# arduino_block.net
KiCad netlist of a schematic drawn in EAGLE
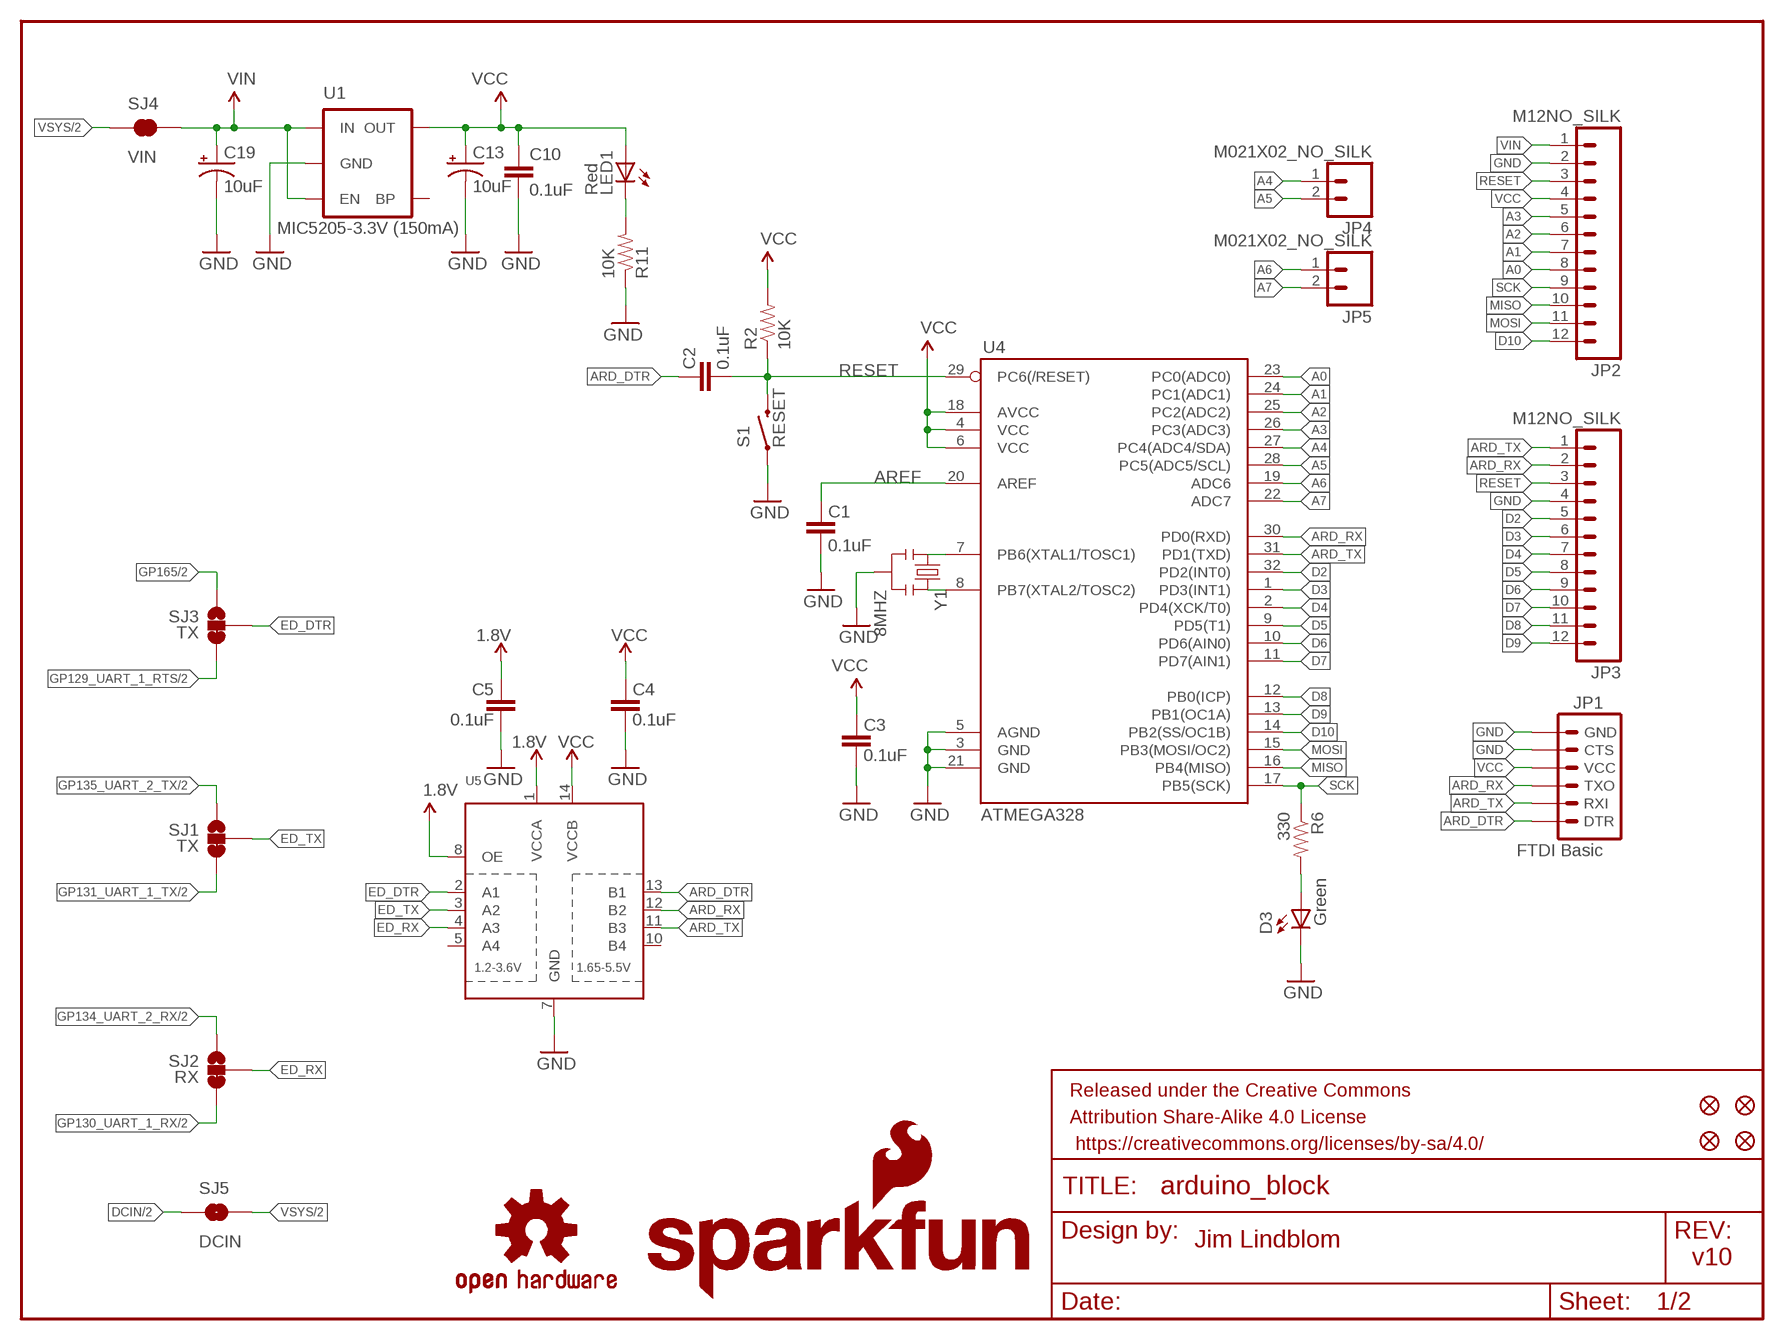
[diagram p0: schematic, sheet 1]
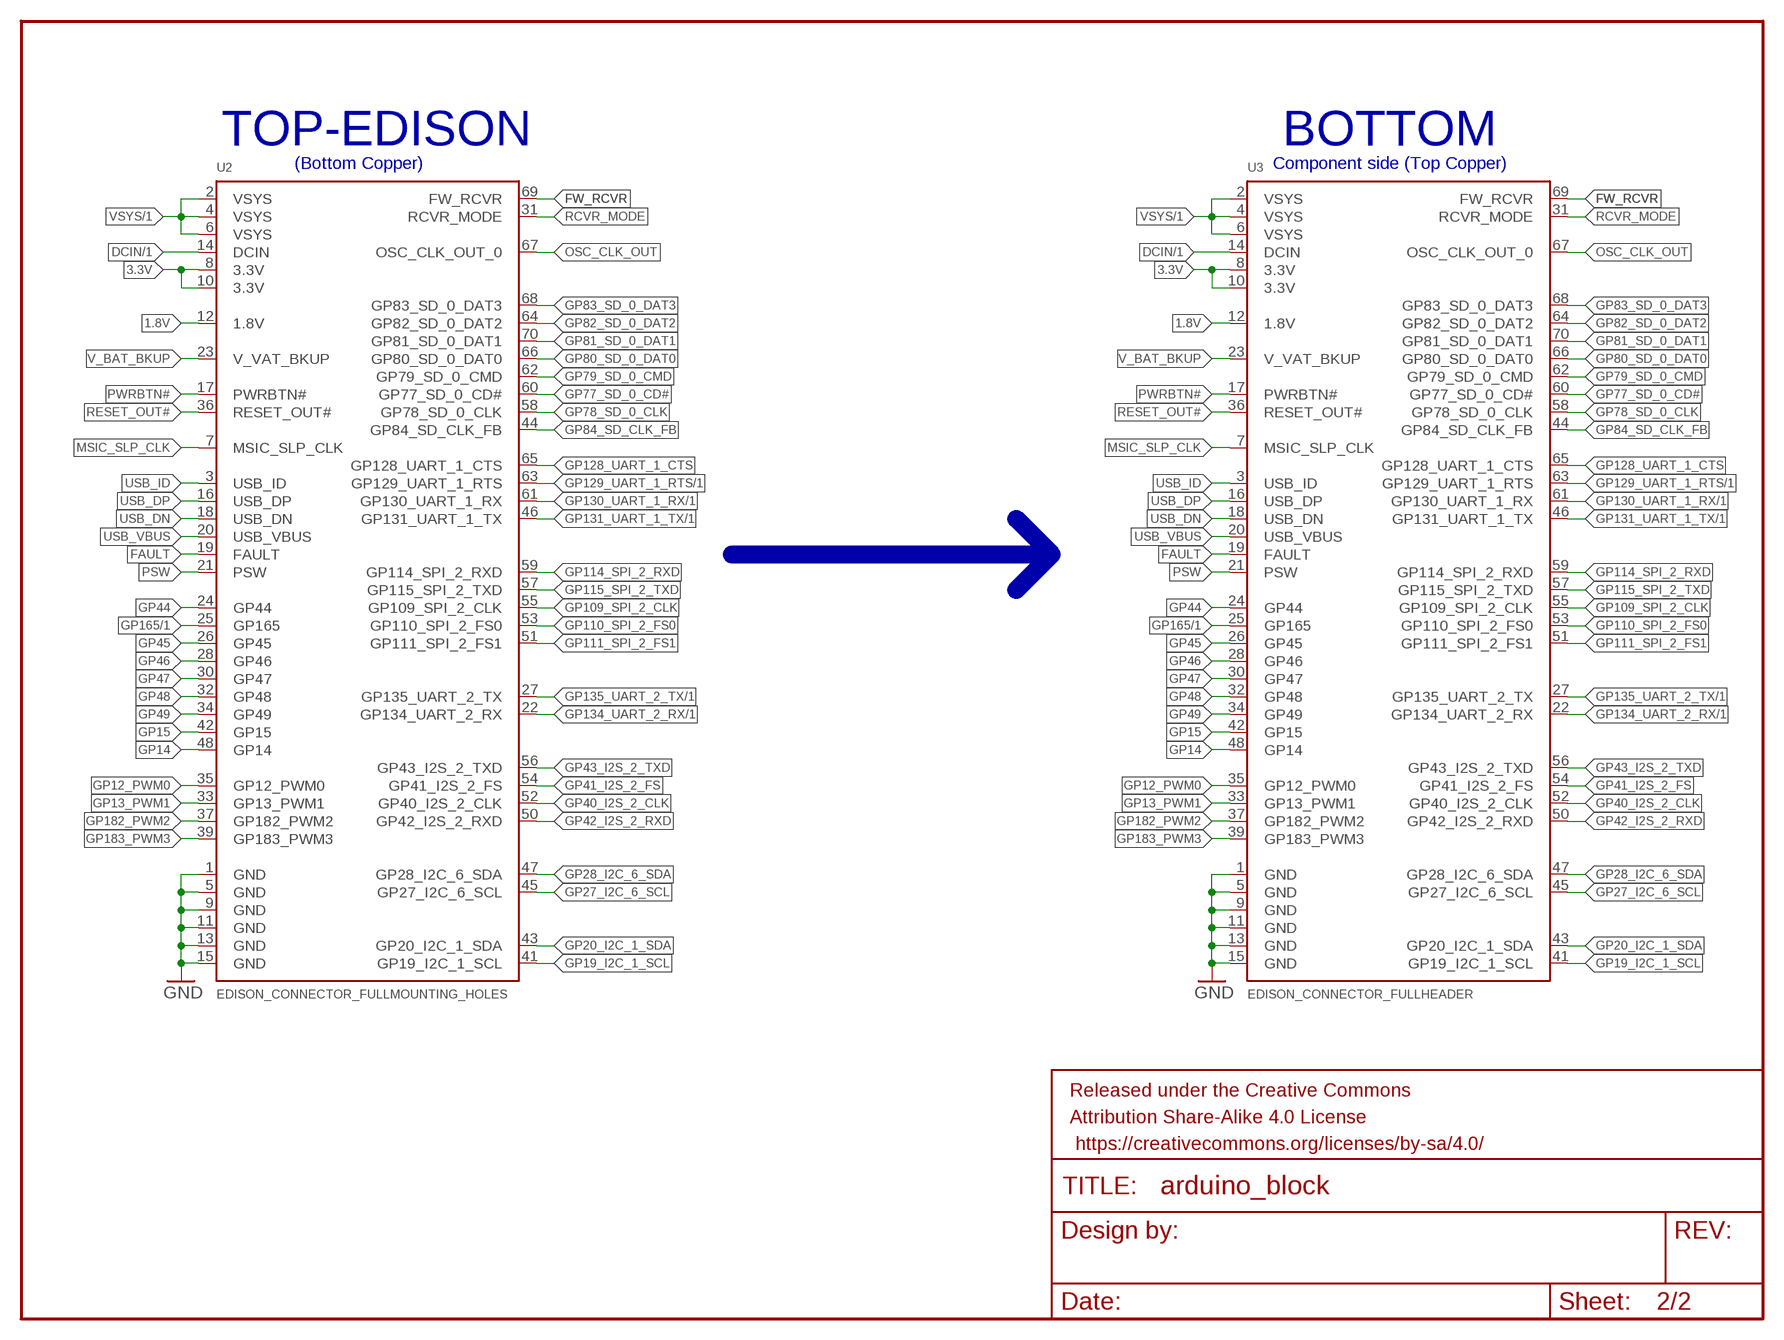
[diagram p1: schematic, sheet 2]

(export (version "E")
  (design (tool "Eeschema 10.0.6"))
  (components
    (comp (ref "C1")
      (value "0.1uF")
      (footprint "eagle-import:0603-CAP")
      (libsource (lib "eagle-import") (part "CAP0603-CAP"))
    )
    (comp (ref "C2")
      (value "0.1uF")
      (footprint "eagle-import:0603-CAP")
      (libsource (lib "eagle-import") (part "CAP0603-CAP"))
    )
    (comp (ref "C3")
      (value "0.1uF")
      (footprint "eagle-import:0603-CAP")
      (libsource (lib "eagle-import") (part "CAP0603-CAP"))
    )
    (comp (ref "C4")
      (value "0.1uF")
      (footprint "eagle-import:0603-CAP")
      (libsource (lib "eagle-import") (part "CAP0603-CAP"))
    )
    (comp (ref "C5")
      (value "0.1uF")
      (footprint "eagle-import:0603-CAP")
      (libsource (lib "eagle-import") (part "CAP0603-CAP"))
    )
    (comp (ref "C10")
      (value "0.1uF")
      (footprint "eagle-import:0603-CAP")
      (libsource (lib "eagle-import") (part "CAP0603-CAP"))
    )
    (comp (ref "C13")
      (value "10uF")
      (footprint "eagle-import:EIA3216")
      (libsource (lib "eagle-import") (part "CAP_POL1206"))
    )
    (comp (ref "C19")
      (value "10uF")
      (footprint "eagle-import:EIA3216")
      (libsource (lib "eagle-import") (part "CAP_POL1206"))
    )
    (comp (ref "D3")
      (value "Green")
      (footprint "eagle-import:0603-LED-ALT1")
      (libsource (lib "eagle-import") (part "LED"))
    )
    (comp (ref "FID1")
      (value "FIDUCIAL1X2")
      (footprint "eagle-import:FIDUCIAL-1X2")
      (libsource (lib "eagle-import") (part "FIDUCIAL1X2"))
    )
    (comp (ref "FID2")
      (value "FIDUCIAL1X2")
      (footprint "eagle-import:FIDUCIAL-1X2")
      (libsource (lib "eagle-import") (part "FIDUCIAL1X2"))
    )
    (comp (ref "FID3")
      (value "FIDUCIAL1X2")
      (footprint "eagle-import:FIDUCIAL-1X2")
      (libsource (lib "eagle-import") (part "FIDUCIAL1X2"))
    )
    (comp (ref "FID4")
      (value "FIDUCIAL1X2")
      (footprint "eagle-import:FIDUCIAL-1X2")
      (libsource (lib "eagle-import") (part "FIDUCIAL1X2"))
    )
    (comp (ref "FRAME1")
      (value "FRAME-LETTER")
      (footprint "eagle-import:CREATIVE_COMMONS")
      (libsource (lib "eagle-import") (part "FRAME-LETTER"))
    )
    (comp (ref "JP1")
      (value "FTDI Basic")
      (footprint "eagle-import:1X06")
      (libsource (lib "eagle-import") (part "ARDUINO_SERIAL_PROGRAMPTH"))
    )
    (comp (ref "JP2")
      (value "M12NO_SILK")
      (footprint "eagle-import:1X12_NO_SILK")
      (libsource (lib "eagle-import") (part "M12NO_SILK"))
    )
    (comp (ref "JP3")
      (value "M12NO_SILK")
      (footprint "eagle-import:1X12_NO_SILK")
      (libsource (lib "eagle-import") (part "M12NO_SILK"))
    )
    (comp (ref "JP4")
      (value "M021X02_NO_SILK")
      (footprint "eagle-import:1X02_NO_SILK")
      (libsource (lib "eagle-import") (part "M021X02_NO_SILK"))
    )
    (comp (ref "JP5")
      (value "M021X02_NO_SILK")
      (footprint "eagle-import:1X02_NO_SILK")
      (libsource (lib "eagle-import") (part "M021X02_NO_SILK"))
    )
    (comp (ref "LED1")
      (value "Red")
      (footprint "eagle-import:0603-LED-ALT1")
      (libsource (lib "eagle-import") (part "LED"))
    )
    (comp (ref "LOGO1")
      (value "OSHW-LOGOS")
      (footprint "eagle-import:OSHW-LOGO-S")
      (libsource (lib "eagle-import") (part "OSHW-LOGOS"))
    )
    (comp (ref "LOGO4")
      (value "SFE_LOGO_NAME_FLAME.1_INCH")
      (footprint "eagle-import:SFE_LOGO_NAME_FLAME_.1")
      (libsource (lib "eagle-import") (part "SFE_LOGO_NAME_FLAME.1_INCH"))
    )
    (comp (ref "R2")
      (value "10K")
      (footprint "eagle-import:0603-RES")
      (libsource (lib "eagle-import") (part "RESISTOR0603-RES"))
    )
    (comp (ref "R6")
      (value "330")
      (footprint "eagle-import:0603-RES")
      (libsource (lib "eagle-import") (part "RESISTOR0603-RES"))
    )
    (comp (ref "R11")
      (value "10K")
      (footprint "eagle-import:0603-RES")
      (libsource (lib "eagle-import") (part "RESISTOR0603-RES"))
    )
    (comp (ref "S1")
      (value "RESET")
      (footprint "eagle-import:TACTILE_SWITCH-SMD-RIGHT-ANGLE")
      (libsource (lib "eagle-import") (part "SWITCH-MOMENTARY-2TACTILE-SWITCH-SMD-RIGHT-ANGLE"))
    )
    (comp (ref "SJ1")
      (value "TX")
      (footprint "eagle-import:PAD-JUMPER-3-2OF3_NC_BY_TRACE_YES_SILK_FULL_BOX")
      (libsource (lib "eagle-import") (part "JUMPER-PAD-3-2OF3_NC_BY_TRACE"))
    )
    (comp (ref "SJ2")
      (value "RX")
      (footprint "eagle-import:PAD-JUMPER-3-2OF3_NC_BY_TRACE_YES_SILK_FULL_BOX")
      (libsource (lib "eagle-import") (part "JUMPER-PAD-3-2OF3_NC_BY_TRACE"))
    )
    (comp (ref "SJ3")
      (value "TX")
      (footprint "eagle-import:PAD-JUMPER-3-2OF3_NC_BY_TRACE_YES_SILK_FULL_BOX")
      (libsource (lib "eagle-import") (part "JUMPER-PAD-3-2OF3_NC_BY_TRACE"))
    )
    (comp (ref "SJ4")
      (value "VIN")
      (footprint "eagle-import:PAD-JUMPER-2-NC_BY_TRACE_YES_SILK")
      (libsource (lib "eagle-import") (part "JUMPER-PAD-2-NC_BY_TRACE"))
    )
    (comp (ref "SJ5")
      (value "DCIN")
      (footprint "eagle-import:PAD-JUMPER-2-NO_YES_SILK")
      (libsource (lib "eagle-import") (part "JUMPER-PAD-2-NOYES_SILK"))
    )
    (comp (ref "U1")
      (value "MIC5205-3.3V (150mA)")
      (footprint "eagle-import:SOT23-5")
      (libsource (lib "eagle-import") (part "V_REG_LDOSMD"))
    )
    (comp (ref "U4")
      (value "ATMEGA328")
      (footprint "eagle-import:TQFP32-08")
      (libsource (lib "eagle-import") (part "ATMEGA168"))
    )
    (comp (ref "U5")
      (value "TXB0104PWRSOIC14")
      (footprint "eagle-import:SO14")
      (libsource (lib "eagle-import") (part "TXB0104PWRSOIC14"))
    )
    (comp (ref "Y1")
      (value "8MHZ")
      (footprint "eagle-import:RESONATOR-SMD")
      (libsource (lib "eagle-import") (part "RESONATOR8MHZ"))
    )
    (comp (ref "FRAME2")
      (value "FRAME-LETTER")
      (footprint "eagle-import:CREATIVE_COMMONS")
      (libsource (lib "eagle-import") (part "FRAME-LETTER"))
    )
    (comp (ref "U2")
      (value "EDISON_CONNECTOR_FULLMOUNTING_HOLES")
      (footprint "eagle-import:EDISON_DAUGHTER")
      (libsource (lib "eagle-import") (part "EDISON_CONNECTOR_FULLMOUNTING_HOLES"))
    )
    (comp (ref "U3")
      (value "EDISON_CONNECTOR_FULLHEADER")
      (footprint "eagle-import:DF40C-70DP-0.4(51)")
      (libsource (lib "eagle-import") (part "EDISON_CONNECTOR_FULLHEADER"))
    )
  )
  (nets
    (net (code "1") (name "1.8V") (class "Default")
      (node (ref "C5") (pin "2") (pinfunction "2_2") (pintype "passive"))
      (node (ref "U2") (pin "12") (pinfunction "1.8V_12") (pintype "bidirectional"))
      (node (ref "U3") (pin "12") (pinfunction "1.8V_12") (pintype "bidirectional"))
      (node (ref "U5") (pin "1") (pinfunction "VCCA_1") (pintype "bidirectional"))
      (node (ref "U5") (pin "8") (pinfunction "OE_8") (pintype "bidirectional"))
    )
    (net (code "2") (name "3.3V") (class "Default")
      (node (ref "U2") (pin "10") (pinfunction "3.3V_10") (pintype "bidirectional"))
      (node (ref "U2") (pin "8") (pinfunction "3.3V_8") (pintype "bidirectional"))
      (node (ref "U3") (pin "10") (pinfunction "3.3V_10") (pintype "bidirectional"))
      (node (ref "U3") (pin "8") (pinfunction "3.3V_8") (pintype "bidirectional"))
    )
    (net (code "3") (name "A0") (class "Default")
      (node (ref "JP2") (pin "8") (pinfunction "8_8") (pintype "passive"))
      (node (ref "U4") (pin "23") (pinfunction "PC0(ADC0)_23") (pintype "bidirectional"))
    )
    (net (code "4") (name "A1") (class "Default")
      (node (ref "JP2") (pin "7") (pinfunction "7_7") (pintype "passive"))
      (node (ref "U4") (pin "24") (pinfunction "PC1(ADC1)_24") (pintype "bidirectional"))
    )
    (net (code "5") (name "A2") (class "Default")
      (node (ref "JP2") (pin "6") (pinfunction "6_6") (pintype "passive"))
      (node (ref "U4") (pin "25") (pinfunction "PC2(ADC2)_25") (pintype "bidirectional"))
    )
    (net (code "6") (name "A3") (class "Default")
      (node (ref "JP2") (pin "5") (pinfunction "5_5") (pintype "passive"))
      (node (ref "U4") (pin "26") (pinfunction "PC3(ADC3)_26") (pintype "bidirectional"))
    )
    (net (code "7") (name "A4") (class "Default")
      (node (ref "JP4") (pin "1") (pinfunction "1_1") (pintype "passive"))
      (node (ref "U4") (pin "27") (pinfunction "PC4(ADC4/SDA)_27") (pintype "bidirectional"))
    )
    (net (code "8") (name "A5") (class "Default")
      (node (ref "JP4") (pin "2") (pinfunction "2_2") (pintype "passive"))
      (node (ref "U4") (pin "28") (pinfunction "PC5(ADC5/SCL)_28") (pintype "bidirectional"))
    )
    (net (code "9") (name "A6") (class "Default")
      (node (ref "JP5") (pin "1") (pinfunction "1_1") (pintype "passive"))
      (node (ref "U4") (pin "19") (pinfunction "ADC6_19") (pintype "bidirectional"))
    )
    (net (code "10") (name "A7") (class "Default")
      (node (ref "JP5") (pin "2") (pinfunction "2_2") (pintype "passive"))
      (node (ref "U4") (pin "22") (pinfunction "ADC7_22") (pintype "bidirectional"))
    )
    (net (code "11") (name "ARD_DTR") (class "Default")
      (node (ref "C2") (pin "2") (pinfunction "2_2") (pintype "passive"))
      (node (ref "JP1") (pin "1") (pinfunction "DTR_1") (pintype "passive"))
      (node (ref "U5") (pin "13") (pinfunction "B1_13") (pintype "bidirectional"))
    )
    (net (code "12") (name "ARD_RX") (class "Default")
      (node (ref "JP1") (pin "3") (pinfunction "TXO_3") (pintype "passive"))
      (node (ref "JP3") (pin "2") (pinfunction "2_2") (pintype "passive"))
      (node (ref "U4") (pin "30") (pinfunction "PD0(RXD)_30") (pintype "bidirectional"))
      (node (ref "U5") (pin "12") (pinfunction "B2_12") (pintype "bidirectional"))
    )
    (net (code "13") (name "ARD_TX") (class "Default")
      (node (ref "JP1") (pin "2") (pinfunction "RXI_2") (pintype "passive"))
      (node (ref "JP3") (pin "1") (pinfunction "1_1") (pintype "passive"))
      (node (ref "U4") (pin "31") (pinfunction "PD1(TXD)_31") (pintype "bidirectional"))
      (node (ref "U5") (pin "11") (pinfunction "B3_11") (pintype "bidirectional"))
    )
    (net (code "14") (name "AREF") (class "Default")
      (node (ref "C1") (pin "2") (pinfunction "2_2") (pintype "passive"))
      (node (ref "U4") (pin "20") (pinfunction "AREF_20") (pintype "bidirectional"))
    )
    (net (code "15") (name "D2") (class "Default")
      (node (ref "JP3") (pin "5") (pinfunction "5_5") (pintype "passive"))
      (node (ref "U4") (pin "32") (pinfunction "PD2(INT0)_32") (pintype "bidirectional"))
    )
    (net (code "16") (name "D3") (class "Default")
      (node (ref "JP3") (pin "6") (pinfunction "6_6") (pintype "passive"))
      (node (ref "U4") (pin "1") (pinfunction "PD3(INT1)_1") (pintype "bidirectional"))
    )
    (net (code "17") (name "D4") (class "Default")
      (node (ref "JP3") (pin "7") (pinfunction "7_7") (pintype "passive"))
      (node (ref "U4") (pin "2") (pinfunction "PD4(XCK/T0)_2") (pintype "bidirectional"))
    )
    (net (code "18") (name "D5") (class "Default")
      (node (ref "JP3") (pin "8") (pinfunction "8_8") (pintype "passive"))
      (node (ref "U4") (pin "9") (pinfunction "PD5(T1)_9") (pintype "bidirectional"))
    )
    (net (code "19") (name "D6") (class "Default")
      (node (ref "JP3") (pin "9") (pinfunction "9_9") (pintype "passive"))
      (node (ref "U4") (pin "10") (pinfunction "PD6(AIN0)_10") (pintype "bidirectional"))
    )
    (net (code "20") (name "D7") (class "Default")
      (node (ref "JP3") (pin "10") (pinfunction "10_10") (pintype "passive"))
      (node (ref "U4") (pin "11") (pinfunction "PD7(AIN1)_11") (pintype "bidirectional"))
    )
    (net (code "21") (name "D8") (class "Default")
      (node (ref "JP3") (pin "11") (pinfunction "11_11") (pintype "passive"))
      (node (ref "U4") (pin "12") (pinfunction "PB0(ICP)_12") (pintype "bidirectional"))
    )
    (net (code "22") (name "D9") (class "Default")
      (node (ref "JP3") (pin "12") (pinfunction "12_12") (pintype "passive"))
      (node (ref "U4") (pin "13") (pinfunction "PB1(OC1A)_13") (pintype "bidirectional"))
    )
    (net (code "23") (name "D10") (class "Default")
      (node (ref "JP2") (pin "12") (pinfunction "12_12") (pintype "passive"))
      (node (ref "U4") (pin "14") (pinfunction "PB2(SS/OC1B)_14") (pintype "bidirectional"))
    )
    (net (code "24") (name "DCIN") (class "Default")
      (node (ref "SJ5") (pin "1") (pinfunction "1_1") (pintype "passive"))
      (node (ref "U2") (pin "14") (pinfunction "DCIN_14") (pintype "bidirectional"))
      (node (ref "U3") (pin "14") (pinfunction "DCIN_14") (pintype "bidirectional"))
    )
    (net (code "25") (name "ED_DTR") (class "Default")
      (node (ref "SJ3") (pin "2") (pinfunction "2_2") (pintype "passive"))
      (node (ref "U5") (pin "2") (pinfunction "A1_2") (pintype "bidirectional"))
    )
    (net (code "26") (name "ED_RX") (class "Default")
      (node (ref "SJ2") (pin "2") (pinfunction "2_2") (pintype "passive"))
      (node (ref "U5") (pin "4") (pinfunction "A3_4") (pintype "bidirectional"))
    )
    (net (code "27") (name "ED_TX") (class "Default")
      (node (ref "SJ1") (pin "2") (pinfunction "2_2") (pintype "passive"))
      (node (ref "U5") (pin "3") (pinfunction "A2_3") (pintype "bidirectional"))
    )
    (net (code "28") (name "FAULT") (class "Default")
      (node (ref "U2") (pin "19") (pinfunction "FAULT_19") (pintype "bidirectional"))
      (node (ref "U3") (pin "19") (pinfunction "FAULT_19") (pintype "bidirectional"))
    )
    (net (code "29") (name "FW_RCVR") (class "Default")
      (node (ref "U2") (pin "69") (pinfunction "FW_RCVR_69") (pintype "bidirectional"))
      (node (ref "U3") (pin "69") (pinfunction "FW_RCVR_69") (pintype "bidirectional"))
    )
    (net (code "30") (name "GND") (class "Default")
      (node (ref "C1") (pin "1") (pinfunction "1_1") (pintype "passive"))
      (node (ref "C10") (pin "2") (pinfunction "2_2") (pintype "passive"))
      (node (ref "C13") (pin "C") (pinfunction "-_C") (pintype "passive"))
      (node (ref "C19") (pin "C") (pinfunction "-_C") (pintype "passive"))
      (node (ref "C3") (pin "1") (pinfunction "1_1") (pintype "passive"))
      (node (ref "C4") (pin "1") (pinfunction "1_1") (pintype "passive"))
      (node (ref "C5") (pin "1") (pinfunction "1_1") (pintype "passive"))
      (node (ref "D3") (pin "C") (pinfunction "C_C") (pintype "passive"))
      (node (ref "JP1") (pin "5") (pinfunction "CTS_5") (pintype "passive"))
      (node (ref "JP1") (pin "6") (pinfunction "GND_6") (pintype "passive"))
      (node (ref "JP2") (pin "2") (pinfunction "2_2") (pintype "passive"))
      (node (ref "JP3") (pin "4") (pinfunction "4_4") (pintype "passive"))
      (node (ref "R11") (pin "1") (pinfunction "1_1") (pintype "passive"))
      (node (ref "S1") (pin "1") (pinfunction "1_1") (pintype "passive"))
      (node (ref "U1") (pin "2") (pinfunction "GND_2") (pintype "input"))
      (node (ref "U2") (pin "1") (pinfunction "GND_1") (pintype "bidirectional"))
      (node (ref "U2") (pin "11") (pinfunction "GND_11") (pintype "bidirectional"))
      (node (ref "U2") (pin "13") (pinfunction "GND_13") (pintype "bidirectional"))
      (node (ref "U2") (pin "15") (pinfunction "GND_15") (pintype "bidirectional"))
      (node (ref "U2") (pin "5") (pinfunction "GND_5") (pintype "bidirectional"))
      (node (ref "U2") (pin "9") (pinfunction "GND_9") (pintype "bidirectional"))
      (node (ref "U3") (pin "1") (pinfunction "GND_1") (pintype "bidirectional"))
      (node (ref "U3") (pin "11") (pinfunction "GND_11") (pintype "bidirectional"))
      (node (ref "U3") (pin "13") (pinfunction "GND_13") (pintype "bidirectional"))
      (node (ref "U3") (pin "15") (pinfunction "GND_15") (pintype "bidirectional"))
      (node (ref "U3") (pin "5") (pinfunction "GND_5") (pintype "bidirectional"))
      (node (ref "U3") (pin "9") (pinfunction "GND_9") (pintype "bidirectional"))
      (node (ref "U4") (pin "21") (pinfunction "GND_21") (pintype "bidirectional"))
      (node (ref "U4") (pin "3") (pinfunction "GND_3") (pintype "bidirectional"))
      (node (ref "U4") (pin "5") (pinfunction "AGND_5") (pintype "bidirectional"))
      (node (ref "U5") (pin "7") (pinfunction "GND_7") (pintype "bidirectional"))
      (node (ref "Y1") (pin "2") (pinfunction "2_2") (pintype "passive"))
    )
    (net (code "31") (name "GP12_PWM0") (class "Default")
      (node (ref "U2") (pin "35") (pinfunction "GP12_PWM0_35") (pintype "bidirectional"))
      (node (ref "U3") (pin "35") (pinfunction "GP12_PWM0_35") (pintype "bidirectional"))
    )
    (net (code "32") (name "GP13_PWM1") (class "Default")
      (node (ref "U2") (pin "33") (pinfunction "GP13_PWM1_33") (pintype "bidirectional"))
      (node (ref "U3") (pin "33") (pinfunction "GP13_PWM1_33") (pintype "bidirectional"))
    )
    (net (code "33") (name "GP14") (class "Default")
      (node (ref "U2") (pin "48") (pinfunction "GP14_48") (pintype "bidirectional"))
      (node (ref "U3") (pin "48") (pinfunction "GP14_48") (pintype "bidirectional"))
    )
    (net (code "34") (name "GP15") (class "Default")
      (node (ref "U2") (pin "42") (pinfunction "GP15_42") (pintype "bidirectional"))
      (node (ref "U3") (pin "42") (pinfunction "GP15_42") (pintype "bidirectional"))
    )
    (net (code "35") (name "GP19_I2C_1_SCL") (class "Default")
      (node (ref "U2") (pin "41") (pinfunction "GP19_I2C_1_SCL_41") (pintype "bidirectional"))
      (node (ref "U3") (pin "41") (pinfunction "GP19_I2C_1_SCL_41") (pintype "bidirectional"))
    )
    (net (code "36") (name "GP20_I2C_1_SDA") (class "Default")
      (node (ref "U2") (pin "43") (pinfunction "GP20_I2C_1_SDA_43") (pintype "bidirectional"))
      (node (ref "U3") (pin "43") (pinfunction "GP20_I2C_1_SDA_43") (pintype "bidirectional"))
    )
    (net (code "37") (name "GP27_I2C_6_SCL") (class "Default")
      (node (ref "U2") (pin "45") (pinfunction "GP27_I2C_6_SCL_45") (pintype "bidirectional"))
      (node (ref "U3") (pin "45") (pinfunction "GP27_I2C_6_SCL_45") (pintype "bidirectional"))
    )
    (net (code "38") (name "GP28_I2C_6_SDA") (class "Default")
      (node (ref "U2") (pin "47") (pinfunction "GP28_I2C_6_SDA_47") (pintype "bidirectional"))
      (node (ref "U3") (pin "47") (pinfunction "GP28_I2C_6_SDA_47") (pintype "bidirectional"))
    )
    (net (code "39") (name "GP40_I2S_2_CLK") (class "Default")
      (node (ref "U2") (pin "52") (pinfunction "GP40_I2S_2_CLK_52") (pintype "bidirectional"))
      (node (ref "U3") (pin "52") (pinfunction "GP40_I2S_2_CLK_52") (pintype "bidirectional"))
    )
    (net (code "40") (name "GP41_I2S_2_FS") (class "Default")
      (node (ref "U2") (pin "54") (pinfunction "GP41_I2S_2_FS_54") (pintype "bidirectional"))
      (node (ref "U3") (pin "54") (pinfunction "GP41_I2S_2_FS_54") (pintype "bidirectional"))
    )
    (net (code "41") (name "GP42_I2S_2_RXD") (class "Default")
      (node (ref "U2") (pin "50") (pinfunction "GP42_I2S_2_RXD_50") (pintype "bidirectional"))
      (node (ref "U3") (pin "50") (pinfunction "GP42_I2S_2_RXD_50") (pintype "bidirectional"))
    )
    (net (code "42") (name "GP43_I2S_2_TXD") (class "Default")
      (node (ref "U2") (pin "56") (pinfunction "GP43_I2S_2_TXD_56") (pintype "bidirectional"))
      (node (ref "U3") (pin "56") (pinfunction "GP43_I2S_2_TXD_56") (pintype "bidirectional"))
    )
    (net (code "43") (name "GP44") (class "Default")
      (node (ref "U2") (pin "24") (pinfunction "GP44_24") (pintype "bidirectional"))
      (node (ref "U3") (pin "24") (pinfunction "GP44_24") (pintype "bidirectional"))
    )
    (net (code "44") (name "GP45") (class "Default")
      (node (ref "U2") (pin "26") (pinfunction "GP45_26") (pintype "bidirectional"))
      (node (ref "U3") (pin "26") (pinfunction "GP45_26") (pintype "bidirectional"))
    )
    (net (code "45") (name "GP46") (class "Default")
      (node (ref "U2") (pin "28") (pinfunction "GP46_28") (pintype "bidirectional"))
      (node (ref "U3") (pin "28") (pinfunction "GP46_28") (pintype "bidirectional"))
    )
    (net (code "46") (name "GP47") (class "Default")
      (node (ref "U2") (pin "30") (pinfunction "GP47_30") (pintype "bidirectional"))
      (node (ref "U3") (pin "30") (pinfunction "GP47_30") (pintype "bidirectional"))
    )
    (net (code "47") (name "GP48") (class "Default")
      (node (ref "U2") (pin "32") (pinfunction "GP48_32") (pintype "bidirectional"))
      (node (ref "U3") (pin "32") (pinfunction "GP48_32") (pintype "bidirectional"))
    )
    (net (code "48") (name "GP49") (class "Default")
      (node (ref "U2") (pin "34") (pinfunction "GP49_34") (pintype "bidirectional"))
      (node (ref "U3") (pin "34") (pinfunction "GP49_34") (pintype "bidirectional"))
    )
    (net (code "49") (name "GP77_SD_0_CD#") (class "Default")
      (node (ref "U2") (pin "60") (pinfunction "GP77_SD_0_CD#_60") (pintype "bidirectional"))
      (node (ref "U3") (pin "60") (pinfunction "GP77_SD_0_CD#_60") (pintype "bidirectional"))
    )
    (net (code "50") (name "GP78_SD_0_CLK") (class "Default")
      (node (ref "U2") (pin "58") (pinfunction "GP78_SD_0_CLK_58") (pintype "bidirectional"))
      (node (ref "U3") (pin "58") (pinfunction "GP78_SD_0_CLK_58") (pintype "bidirectional"))
    )
    (net (code "51") (name "GP79_SD_0_CMD") (class "Default")
      (node (ref "U2") (pin "62") (pinfunction "GP79_SD_0_CMD_62") (pintype "bidirectional"))
      (node (ref "U3") (pin "62") (pinfunction "GP79_SD_0_CMD_62") (pintype "bidirectional"))
    )
    (net (code "52") (name "GP80_SD_0_DAT0") (class "Default")
      (node (ref "U2") (pin "66") (pinfunction "GP80_SD_0_DAT0_66") (pintype "bidirectional"))
      (node (ref "U3") (pin "66") (pinfunction "GP80_SD_0_DAT0_66") (pintype "bidirectional"))
    )
    (net (code "53") (name "GP81_SD_0_DAT1") (class "Default")
      (node (ref "U2") (pin "70") (pinfunction "GP81_SD_0_DAT1_70") (pintype "bidirectional"))
      (node (ref "U3") (pin "70") (pinfunction "GP81_SD_0_DAT1_70") (pintype "bidirectional"))
    )
    (net (code "54") (name "GP82_SD_0_DAT2") (class "Default")
      (node (ref "U2") (pin "64") (pinfunction "GP82_SD_0_DAT2_64") (pintype "bidirectional"))
      (node (ref "U3") (pin "64") (pinfunction "GP82_SD_0_DAT2_64") (pintype "bidirectional"))
    )
    (net (code "55") (name "GP83_SD_0_DAT3") (class "Default")
      (node (ref "U2") (pin "68") (pinfunction "GP83_SD_0_DAT3_68") (pintype "bidirectional"))
      (node (ref "U3") (pin "68") (pinfunction "GP83_SD_0_DAT3_68") (pintype "bidirectional"))
    )
    (net (code "56") (name "GP84_SD_CLK_FB") (class "Default")
      (node (ref "U2") (pin "44") (pinfunction "GP84_SD_CLK_FB_44") (pintype "bidirectional"))
      (node (ref "U3") (pin "44") (pinfunction "GP84_SD_CLK_FB_44") (pintype "bidirectional"))
    )
    (net (code "57") (name "GP109_SPI_2_CLK") (class "Default")
      (node (ref "U2") (pin "55") (pinfunction "GP109_SPI_2_CLK_55") (pintype "bidirectional"))
      (node (ref "U3") (pin "55") (pinfunction "GP109_SPI_2_CLK_55") (pintype "bidirectional"))
    )
    (net (code "58") (name "GP110_SPI_2_FS0") (class "Default")
      (node (ref "U2") (pin "53") (pinfunction "GP110_SPI_2_FS0_53") (pintype "bidirectional"))
      (node (ref "U3") (pin "53") (pinfunction "GP110_SPI_2_FS0_53") (pintype "bidirectional"))
    )
    (net (code "59") (name "GP111_SPI_2_FS1") (class "Default")
      (node (ref "U2") (pin "51") (pinfunction "GP111_SPI_2_FS1_51") (pintype "bidirectional"))
      (node (ref "U3") (pin "51") (pinfunction "GP111_SPI_2_FS1_51") (pintype "bidirectional"))
    )
    (net (code "60") (name "GP114_SPI_2_RXD") (class "Default")
      (node (ref "U2") (pin "59") (pinfunction "GP114_SPI_2_RXD_59") (pintype "bidirectional"))
      (node (ref "U3") (pin "59") (pinfunction "GP114_SPI_2_RXD_59") (pintype "bidirectional"))
    )
    (net (code "61") (name "GP115_SPI_2_TXD") (class "Default")
      (node (ref "U2") (pin "57") (pinfunction "GP115_SPI_2_TXD_57") (pintype "bidirectional"))
      (node (ref "U3") (pin "57") (pinfunction "GP115_SPI_2_TXD_57") (pintype "bidirectional"))
    )
    (net (code "62") (name "GP128_UART_1_CTS") (class "Default")
      (node (ref "U2") (pin "65") (pinfunction "GP128_UART_1_CTS_65") (pintype "bidirectional"))
      (node (ref "U3") (pin "65") (pinfunction "GP128_UART_1_CTS_65") (pintype "bidirectional"))
    )
    (net (code "63") (name "GP129_UART_1_RTS") (class "Default")
      (node (ref "SJ3") (pin "3") (pinfunction "3_3") (pintype "passive"))
      (node (ref "U2") (pin "63") (pinfunction "GP129_UART_1_RTS_63") (pintype "bidirectional"))
      (node (ref "U3") (pin "63") (pinfunction "GP129_UART_1_RTS_63") (pintype "bidirectional"))
    )
    (net (code "64") (name "GP130_UART_1_RX") (class "Default")
      (node (ref "SJ2") (pin "3") (pinfunction "3_3") (pintype "passive"))
      (node (ref "U2") (pin "61") (pinfunction "GP130_UART_1_RX_61") (pintype "bidirectional"))
      (node (ref "U3") (pin "61") (pinfunction "GP130_UART_1_RX_61") (pintype "bidirectional"))
    )
    (net (code "65") (name "GP131_UART_1_TX") (class "Default")
      (node (ref "SJ1") (pin "3") (pinfunction "3_3") (pintype "passive"))
      (node (ref "U2") (pin "46") (pinfunction "GP131_UART_1_TX_46") (pintype "bidirectional"))
      (node (ref "U3") (pin "46") (pinfunction "GP131_UART_1_TX_46") (pintype "bidirectional"))
    )
    (net (code "66") (name "GP134_UART_2_RX") (class "Default")
      (node (ref "SJ2") (pin "1") (pinfunction "1_1") (pintype "passive"))
      (node (ref "U2") (pin "22") (pinfunction "GP134_UART_2_RX_22") (pintype "bidirectional"))
      (node (ref "U3") (pin "22") (pinfunction "GP134_UART_2_RX_22") (pintype "bidirectional"))
    )
    (net (code "67") (name "GP135_UART_2_TX") (class "Default")
      (node (ref "SJ1") (pin "1") (pinfunction "1_1") (pintype "passive"))
      (node (ref "U2") (pin "27") (pinfunction "GP135_UART_2_TX_27") (pintype "bidirectional"))
      (node (ref "U3") (pin "27") (pinfunction "GP135_UART_2_TX_27") (pintype "bidirectional"))
    )
    (net (code "68") (name "GP165") (class "Default")
      (node (ref "SJ3") (pin "1") (pinfunction "1_1") (pintype "passive"))
      (node (ref "U2") (pin "25") (pinfunction "GP165_25") (pintype "bidirectional"))
      (node (ref "U3") (pin "25") (pinfunction "GP165_25") (pintype "bidirectional"))
    )
    (net (code "69") (name "GP182_PWM2") (class "Default")
      (node (ref "U2") (pin "37") (pinfunction "GP182_PWM2_37") (pintype "bidirectional"))
      (node (ref "U3") (pin "37") (pinfunction "GP182_PWM2_37") (pintype "bidirectional"))
    )
    (net (code "70") (name "GP183_PWM3") (class "Default")
      (node (ref "U2") (pin "39") (pinfunction "GP183_PWM3_39") (pintype "bidirectional"))
      (node (ref "U3") (pin "39") (pinfunction "GP183_PWM3_39") (pintype "bidirectional"))
    )
    (net (code "71") (name "MISO") (class "Default")
      (node (ref "JP2") (pin "10") (pinfunction "10_10") (pintype "passive"))
      (node (ref "U4") (pin "16") (pinfunction "PB4(MISO)_16") (pintype "bidirectional"))
    )
    (net (code "72") (name "MOSI") (class "Default")
      (node (ref "JP2") (pin "11") (pinfunction "11_11") (pintype "passive"))
      (node (ref "U4") (pin "15") (pinfunction "PB3(MOSI/OC2)_15") (pintype "bidirectional"))
    )
    (net (code "73") (name "MSIC_SLP_CLK") (class "Default")
      (node (ref "U2") (pin "7") (pinfunction "MSIC_SLP_CLK_7") (pintype "bidirectional"))
      (node (ref "U3") (pin "7") (pinfunction "MSIC_SLP_CLK_7") (pintype "bidirectional"))
    )
    (net (code "74") (name "Net-(D3-PadA)") (class "Default")
      (node (ref "D3") (pin "A") (pinfunction "A_A") (pintype "passive"))
      (node (ref "R6") (pin "2") (pinfunction "2_2") (pintype "passive"))
    )
    (net (code "75") (name "Net-(LED1-PadC)") (class "Default")
      (node (ref "LED1") (pin "C") (pinfunction "C_C") (pintype "passive"))
      (node (ref "R11") (pin "2") (pinfunction "2_2") (pintype "passive"))
    )
    (net (code "76") (name "Net-(U4-PB6(XTAL1{slash}TOSC1))") (class "Default")
      (node (ref "U4") (pin "7") (pinfunction "PB6(XTAL1/TOSC1)_7") (pintype "bidirectional"))
      (node (ref "Y1") (pin "1") (pinfunction "1_1") (pintype "passive"))
    )
    (net (code "77") (name "Net-(U4-PB7(XTAL2{slash}TOSC2))") (class "Default")
      (node (ref "U4") (pin "8") (pinfunction "PB7(XTAL2/TOSC2)_8") (pintype "bidirectional"))
      (node (ref "Y1") (pin "3") (pinfunction "3_3") (pintype "passive"))
    )
    (net (code "78") (name "OSC_CLK_OUT") (class "Default")
      (node (ref "U2") (pin "67") (pinfunction "OSC_CLK_OUT_0_67") (pintype "bidirectional"))
      (node (ref "U3") (pin "67") (pinfunction "OSC_CLK_OUT_0_67") (pintype "bidirectional"))
    )
    (net (code "79") (name "PSW") (class "Default")
      (node (ref "U2") (pin "21") (pinfunction "PSW_21") (pintype "bidirectional"))
      (node (ref "U3") (pin "21") (pinfunction "PSW_21") (pintype "bidirectional"))
    )
    (net (code "80") (name "PWRBTN#") (class "Default")
      (node (ref "U2") (pin "17") (pinfunction "PWRBTN#_17") (pintype "bidirectional"))
      (node (ref "U3") (pin "17") (pinfunction "PWRBTN#_17") (pintype "bidirectional"))
    )
    (net (code "81") (name "RCVR_MODE") (class "Default")
      (node (ref "U2") (pin "31") (pinfunction "RCVR_MODE_31") (pintype "bidirectional"))
      (node (ref "U3") (pin "31") (pinfunction "RCVR_MODE_31") (pintype "bidirectional"))
    )
    (net (code "82") (name "RESET") (class "Default")
      (node (ref "C2") (pin "1") (pinfunction "1_1") (pintype "passive"))
      (node (ref "JP2") (pin "3") (pinfunction "3_3") (pintype "passive"))
      (node (ref "JP3") (pin "3") (pinfunction "3_3") (pintype "passive"))
      (node (ref "R2") (pin "1") (pinfunction "1_1") (pintype "passive"))
      (node (ref "S1") (pin "2") (pinfunction "2_2") (pintype "passive"))
      (node (ref "U4") (pin "29") (pinfunction "PC6(/RESET)_29") (pintype "bidirectional"))
    )
    (net (code "83") (name "RESET_OUT#") (class "Default")
      (node (ref "U2") (pin "36") (pinfunction "RESET_OUT#_36") (pintype "bidirectional"))
      (node (ref "U3") (pin "36") (pinfunction "RESET_OUT#_36") (pintype "bidirectional"))
    )
    (net (code "84") (name "SCK") (class "Default")
      (node (ref "JP2") (pin "9") (pinfunction "9_9") (pintype "passive"))
      (node (ref "R6") (pin "1") (pinfunction "1_1") (pintype "passive"))
      (node (ref "U4") (pin "17") (pinfunction "PB5(SCK)_17") (pintype "bidirectional"))
    )
    (net (code "85") (name "USB_DN") (class "Default")
      (node (ref "U2") (pin "18") (pinfunction "USB_DN_18") (pintype "bidirectional"))
      (node (ref "U3") (pin "18") (pinfunction "USB_DN_18") (pintype "bidirectional"))
    )
    (net (code "86") (name "USB_DP") (class "Default")
      (node (ref "U2") (pin "16") (pinfunction "USB_DP_16") (pintype "bidirectional"))
      (node (ref "U3") (pin "16") (pinfunction "USB_DP_16") (pintype "bidirectional"))
    )
    (net (code "87") (name "USB_ID") (class "Default")
      (node (ref "U2") (pin "3") (pinfunction "USB_ID_3") (pintype "bidirectional"))
      (node (ref "U3") (pin "3") (pinfunction "USB_ID_3") (pintype "bidirectional"))
    )
    (net (code "88") (name "USB_VBUS") (class "Default")
      (node (ref "U2") (pin "20") (pinfunction "USB_VBUS_20") (pintype "bidirectional"))
      (node (ref "U3") (pin "20") (pinfunction "USB_VBUS_20") (pintype "bidirectional"))
    )
    (net (code "89") (name "VCC") (class "Default")
      (node (ref "C10") (pin "1") (pinfunction "1_1") (pintype "passive"))
      (node (ref "C13") (pin "A") (pinfunction "+_A") (pintype "passive"))
      (node (ref "C3") (pin "2") (pinfunction "2_2") (pintype "passive"))
      (node (ref "C4") (pin "2") (pinfunction "2_2") (pintype "passive"))
      (node (ref "JP1") (pin "4") (pinfunction "VCC_4") (pintype "passive"))
      (node (ref "JP2") (pin "4") (pinfunction "4_4") (pintype "passive"))
      (node (ref "LED1") (pin "A") (pinfunction "A_A") (pintype "passive"))
      (node (ref "R2") (pin "2") (pinfunction "2_2") (pintype "passive"))
      (node (ref "U1") (pin "5") (pinfunction "OUT_5") (pintype "passive"))
      (node (ref "U4") (pin "18") (pinfunction "AVCC_18") (pintype "bidirectional"))
      (node (ref "U4") (pin "4") (pinfunction "VCC_4") (pintype "bidirectional"))
      (node (ref "U4") (pin "6") (pinfunction "VCC_6") (pintype "bidirectional"))
      (node (ref "U5") (pin "14") (pinfunction "VCCB_14") (pintype "bidirectional"))
    )
    (net (code "90") (name "VIN") (class "Default")
      (node (ref "C19") (pin "A") (pinfunction "+_A") (pintype "passive"))
      (node (ref "JP2") (pin "1") (pinfunction "1_1") (pintype "passive"))
      (node (ref "SJ4") (pin "2") (pinfunction "2_2") (pintype "passive"))
      (node (ref "U1") (pin "1") (pinfunction "IN_1") (pintype "input"))
      (node (ref "U1") (pin "3") (pinfunction "EN_3") (pintype "input"))
    )
    (net (code "91") (name "VSYS") (class "Default")
      (node (ref "SJ4") (pin "1") (pinfunction "1_1") (pintype "passive"))
      (node (ref "SJ5") (pin "2") (pinfunction "2_2") (pintype "passive"))
      (node (ref "U2") (pin "2") (pinfunction "VSYS_2") (pintype "bidirectional"))
      (node (ref "U2") (pin "4") (pinfunction "VSYS_4") (pintype "bidirectional"))
      (node (ref "U2") (pin "6") (pinfunction "VSYS_6") (pintype "bidirectional"))
      (node (ref "U3") (pin "2") (pinfunction "VSYS_2") (pintype "bidirectional"))
      (node (ref "U3") (pin "4") (pinfunction "VSYS_4") (pintype "bidirectional"))
      (node (ref "U3") (pin "6") (pinfunction "VSYS_6") (pintype "bidirectional"))
    )
    (net (code "92") (name "V_BAT_BKUP") (class "Default")
      (node (ref "U2") (pin "23") (pinfunction "V_VAT_BKUP_23") (pintype "bidirectional"))
      (node (ref "U3") (pin "23") (pinfunction "V_VAT_BKUP_23") (pintype "bidirectional"))
    )
    (net (code "93") (name "unconnected-(U1-BP-Pad4)") (class "Default")
      (node (ref "U1") (pin "4") (pinfunction "BP_4") (pintype "input"))
    )
    (net (code "94") (name "unconnected-(U5-A4-Pad5)") (class "Default")
      (node (ref "U5") (pin "5") (pinfunction "A4_5") (pintype "bidirectional"))
    )
    (net (code "95") (name "unconnected-(U5-B4-Pad10)") (class "Default")
      (node (ref "U5") (pin "10") (pinfunction "B4_10") (pintype "bidirectional"))
    )
  )
)
